# Schematic_skinbot_master_v4.net
KiCad netlist of a schematic drawn in Altium Designer
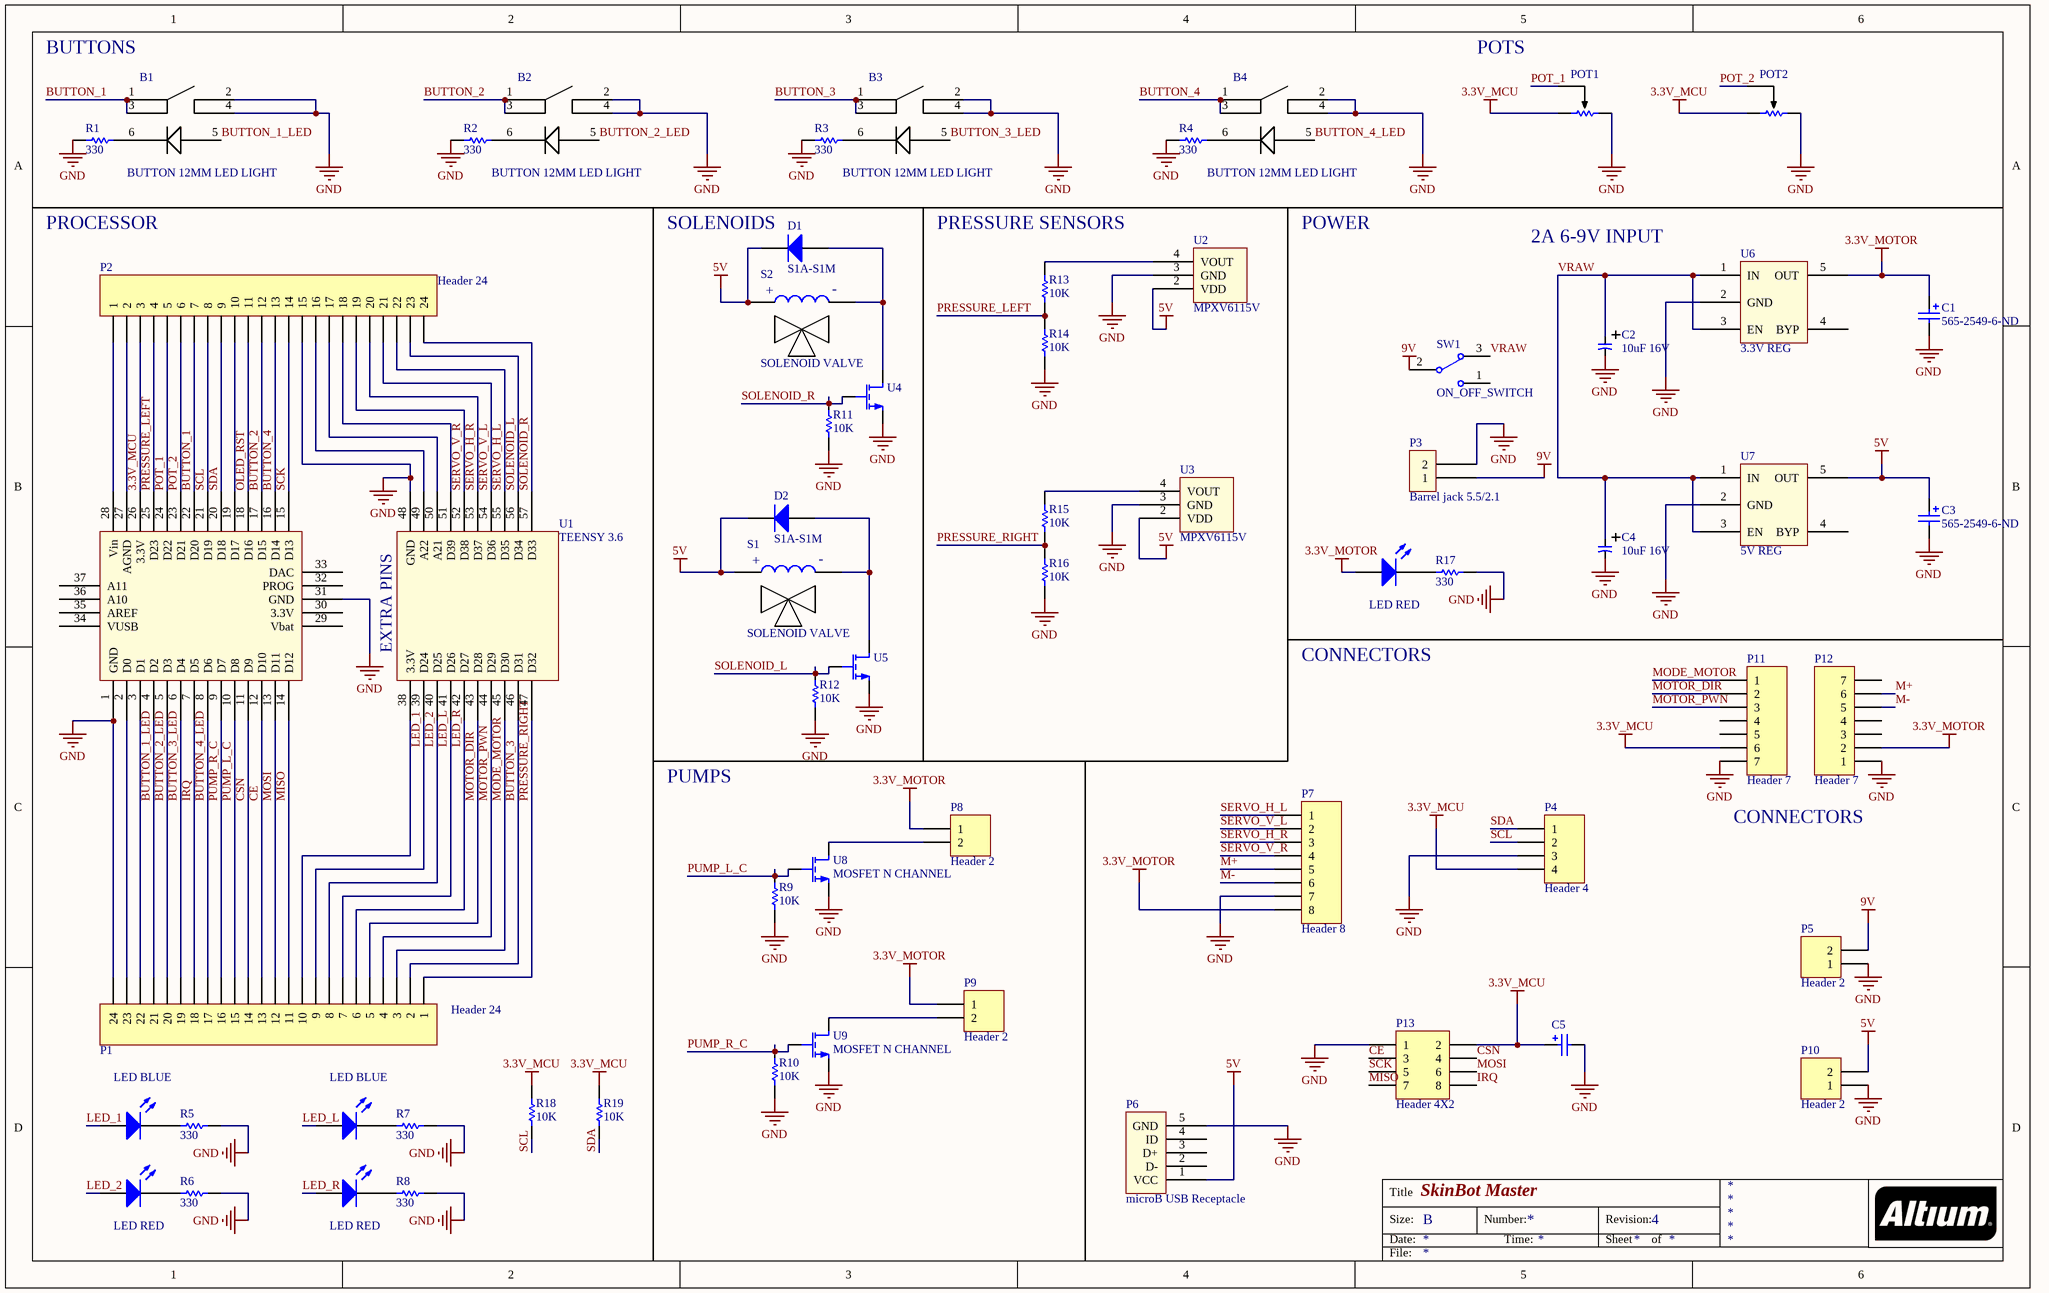
[diagram p0: Schematic_skinbot_master_v4.SchDoc]

(export (version "E")
  (design (tool "Eeschema 10.0.6"))
  (components
    (comp (ref "B1")
      (value "BUTTON 12MM LED LIGHT")
      (footprint "12MM BUTTON LED LIGHT")
      (libsource (lib "Artem_Library") (part "BUTTON 12MM LED LIGHT"))
    )
    (comp (ref "B2")
      (value "BUTTON 12MM LED LIGHT")
      (footprint "12MM BUTTON LED LIGHT")
      (libsource (lib "Artem_Library") (part "BUTTON 12MM LED LIGHT"))
    )
    (comp (ref "B3")
      (value "BUTTON 12MM LED LIGHT")
      (footprint "12MM BUTTON LED LIGHT")
      (libsource (lib "Artem_Library") (part "BUTTON 12MM LED LIGHT"))
    )
    (comp (ref "B4")
      (value "BUTTON 12MM LED LIGHT")
      (footprint "12MM BUTTON LED LIGHT")
      (libsource (lib "Artem_Library") (part "BUTTON 12MM LED LIGHT"))
    )
    (comp (ref "C1")
      (value "Electrolytic Cap 100uF smd")
      (footprint "F80 Electrolytic cap")
      (description "100uF 25 VSMD")
      (fields
        (field (name "DIGIKEY PART NUMBER") "565-2549-1-ND")
        (field (name "MANUFACTURER") "United Chemi-Con")
        (field (name "SUPPLIER PART NUMBER 1") "565-2549-6-ND")
      )
      (libsource (lib "Artem_Library") (part "Electrolytic Cap 100uF smd"))
    )
    (comp (ref "C2")
      (value "10uF 16V")
      (footprint "CAP0805")
      (libsource (lib "Artem_Library") (part "Polarized Cap"))
    )
    (comp (ref "C3")
      (value "Electrolytic Cap 100uF smd")
      (footprint "F80 Electrolytic cap")
      (description "100uF 25 VSMD")
      (fields
        (field (name "DIGIKEY PART NUMBER") "565-2549-1-ND")
        (field (name "MANUFACTURER") "United Chemi-Con")
        (field (name "SUPPLIER PART NUMBER 1") "565-2549-6-ND")
      )
      (libsource (lib "Artem_Library") (part "Electrolytic Cap 100uF smd"))
    )
    (comp (ref "C4")
      (value "10uF 16V")
      (footprint "CAP0805")
      (libsource (lib "Artem_Library") (part "Polarized Cap"))
    )
    (comp (ref "C5")
      (value "Electrolytic Cap 100uF smd")
      (footprint "F80 Electrolytic cap")
      (description "100uF 25 VSMD")
      (fields
        (field (name "DIGIKEY PART NUMBER") "565-2549-1-ND")
        (field (name "MANUFACTURER") "United Chemi-Con")
      )
      (libsource (lib "Artem_Library") (part "Electrolytic Cap 100uF smd"))
    )
    (comp (ref "D1")
      (value "S1A-S1M")
      (footprint "JEDEC DO-214")
      (description "General purpose diode 50V 1A SMA")
      (libsource (lib "Artem_Library") (part "S1A-S1M"))
    )
    (comp (ref "D2")
      (value "S1A-S1M")
      (footprint "JEDEC DO-214")
      (description "General purpose diode 50V 1A SMA")
      (libsource (lib "Artem_Library") (part "S1A-S1M"))
    )
    (comp (ref "LED1")
      (value "LED BLUE")
      (footprint "0603 LED")
      (description "LED SMD 1206/0603")
      (libsource (lib "Artem_Library") (part "LED"))
    )
    (comp (ref "LED2")
      (value "LED RED")
      (footprint "0603 LED")
      (description "LED SMD 1206/0603")
      (libsource (lib "Artem_Library") (part "LED"))
    )
    (comp (ref "LED3")
      (value "LED BLUE")
      (footprint "0603 LED")
      (description "LED SMD 1206/0603")
      (libsource (lib "Artem_Library") (part "LED"))
    )
    (comp (ref "LED4")
      (value "LED RED")
      (footprint "0603 LED")
      (description "LED SMD 1206/0603")
      (libsource (lib "Artem_Library") (part "LED"))
    )
    (comp (ref "LED5")
      (value "LED RED")
      (footprint "0603 LED")
      (description "LED SMD 1206/0603")
      (libsource (lib "Artem_Library") (part "LED"))
    )
    (comp (ref "P1")
      (value "Header 24")
      (footprint "HDR1X24")
      (description "Header, 24-Pin")
      (fields (field (name "PUBLISHER") "Altium Limited"))
      (libsource (lib "") (part "Header 24_1"))
    )
    (comp (ref "P2")
      (value "Header 24")
      (footprint "HDR1X24")
      (description "Header, 24-Pin")
      (fields (field (name "PUBLISHER") "Altium Limited"))
      (libsource (lib "Miscellaneous Connectors") (part "Header 24"))
    )
    (comp (ref "P3")
      (value "Barrel jack 5.5/2.1")
      (footprint "ADC-028-2")
      (fields (field (name "SPARKFUN PART NUMBER") "12748"))
      (libsource (lib "Artem_Library") (part "Barrel jack 5.5/2.1"))
    )
    (comp (ref "P4")
      (value "Header 4")
      (footprint "HDR1X4")
      (description "Header, 4-Pin")
      (fields (field (name "PUBLISHER") "Altium Limited"))
      (libsource (lib "Miscellaneous Connectors") (part "Header 4"))
    )
    (comp (ref "P5")
      (value "Header 2")
      (footprint "HDR1X2")
      (description "Header, 2-Pin")
      (fields (field (name "PUBLISHER") "Altium Limited"))
      (libsource (lib "Miscellaneous Connectors") (part "Header 2"))
    )
    (comp (ref "P6")
      (value "microB USB Receptacle")
      (footprint "MicroB USB Standarad SMT")
      (fields (field (name "MANUFACTURER") "ZX62-B-5PA(11)"))
      (libsource (lib "Artem_Library") (part "microB USB Receptacle"))
    )
    (comp (ref "P7")
      (value "Header 8")
      (footprint "HDR1X8")
      (description "Header, 8-Pin")
      (fields (field (name "PUBLISHER") "Altium Limited"))
      (libsource (lib "Miscellaneous Connectors") (part "Header 8"))
    )
    (comp (ref "P8")
      (value "Header 2")
      (footprint "HDR1X2")
      (description "Header, 2-Pin")
      (fields (field (name "PUBLISHER") "Altium Limited"))
      (libsource (lib "") (part "Header 2_1"))
    )
    (comp (ref "P9")
      (value "Header 2")
      (footprint "HDR1X2")
      (description "Header, 2-Pin")
      (fields (field (name "PUBLISHER") "Altium Limited"))
      (libsource (lib "") (part "Header 2_1"))
    )
    (comp (ref "P10")
      (value "Header 2")
      (footprint "HDR1X2")
      (description "Header, 2-Pin")
      (fields (field (name "PUBLISHER") "Altium Limited"))
      (libsource (lib "Miscellaneous Connectors") (part "Header 2"))
    )
    (comp (ref "P11")
      (value "Header 7")
      (footprint "HDR1X7")
      (description "Header, 7-Pin")
      (fields (field (name "PUBLISHER") "Altium Limited"))
      (libsource (lib "") (part "Header 7_1"))
    )
    (comp (ref "P12")
      (value "Header 7")
      (footprint "HDR1X7")
      (description "Header, 7-Pin")
      (fields (field (name "PUBLISHER") "Altium Limited"))
      (libsource (lib "Miscellaneous Connectors") (part "Header 7"))
    )
    (comp (ref "P13")
      (value "Header 4X2")
      (footprint "HDR2X4")
      (description "Header, 4-Pin, Dual row")
      (fields (field (name "PUBLISHER") "Altium Limited"))
      (libsource (lib "Miscellaneous Connectors") (part "Header 4X2"))
    )
    (comp (ref "POT1")
      (value "Potentiometer large")
      (footprint "PRS11S")
      (description "SMD Large pot for audio")
      (libsource (lib "Artem_Library") (part "Potentiometer large"))
    )
    (comp (ref "POT2")
      (value "Potentiometer large")
      (footprint "PRS11S")
      (description "SMD Large pot for audio")
      (libsource (lib "Artem_Library") (part "Potentiometer large"))
    )
    (comp (ref "R1") (value "330") (footprint "0603W") (libsource (lib "Artem_Library") (part "Resistor")))
    (comp (ref "R2") (value "330") (footprint "0603W") (libsource (lib "Artem_Library") (part "Resistor")))
    (comp (ref "R3") (value "330") (footprint "0603W") (libsource (lib "Artem_Library") (part "Resistor")))
    (comp (ref "R4") (value "330") (footprint "0603W") (libsource (lib "Artem_Library") (part "Resistor")))
    (comp (ref "R5") (value "330") (footprint "0603W") (libsource (lib "Artem_Library") (part "Resistor")))
    (comp (ref "R6") (value "330") (footprint "0603W") (libsource (lib "Artem_Library") (part "Resistor")))
    (comp (ref "R7") (value "330") (footprint "0603W") (libsource (lib "Artem_Library") (part "Resistor")))
    (comp (ref "R8") (value "330") (footprint "0603W") (libsource (lib "Artem_Library") (part "Resistor")))
    (comp (ref "R9") (value "10K") (footprint "0603W") (libsource (lib "Artem_Library") (part "Resistor")))
    (comp (ref "R10") (value "10K") (footprint "0603W") (libsource (lib "Artem_Library") (part "Resistor")))
    (comp (ref "R11") (value "10K") (footprint "0603W") (libsource (lib "Artem_Library") (part "Resistor")))
    (comp (ref "R12") (value "10K") (footprint "0603W") (libsource (lib "Artem_Library") (part "Resistor")))
    (comp (ref "R13") (value "10K") (footprint "0603W") (libsource (lib "Artem_Library") (part "Resistor")))
    (comp (ref "R14") (value "10K") (footprint "0603W") (libsource (lib "Artem_Library") (part "Resistor")))
    (comp (ref "R15") (value "10K") (footprint "0603W") (libsource (lib "Artem_Library") (part "Resistor")))
    (comp (ref "R16") (value "10K") (footprint "0603W") (libsource (lib "Artem_Library") (part "Resistor")))
    (comp (ref "R17") (value "330") (footprint "0603W") (libsource (lib "Artem_Library") (part "Resistor")))
    (comp (ref "R18") (value "10K") (footprint "0603W") (libsource (lib "Artem_Library") (part "Resistor")))
    (comp (ref "R19") (value "10K") (footprint "0603W") (libsource (lib "Artem_Library") (part "Resistor")))
    (comp (ref "S1")
      (value "SOLENOID VALVE")
      (footprint "S070C-5CG-32")
      (libsource (lib "Artem_Library") (part "SOLENOID VALVE"))
    )
    (comp (ref "S2")
      (value "SOLENOID VALVE")
      (footprint "S070C-5CG-32")
      (libsource (lib "Artem_Library") (part "SOLENOID VALVE"))
    )
    (comp (ref "SW1")
      (value "ON_OFF_SWITCH")
      (footprint "SS321 Switch")
      (description "SPDT SMD Side Switch")
      (libsource (lib "Artem_Library") (part "ON_OFF_SWITCH"))
    )
    (comp (ref "U1")
      (value "TEENSY 3.6")
      (footprint "TEENSY 3.6")
      (libsource (lib "Artem_Library") (part "TEENSY 3.6"))
    )
    (comp (ref "U2")
      (value "MPXV6115V")
      (footprint "MPXV6115V")
      (description "Vacuum pressure sensor -115kPa")
      (libsource (lib "Artem_Library") (part "MPXV6115V"))
    )
    (comp (ref "U3")
      (value "MPXV6115V")
      (footprint "MPXV6115V")
      (description "Vacuum pressure sensor -115kPa")
      (libsource (lib "Artem_Library") (part "MPXV6115V"))
    )
    (comp (ref "U4")
      (value "MOSFET N CHANNEL")
      (footprint "SOT323")
      (fields (field (name "DIGIKEY PART NUMBER") "1727-4793-1-ND"))
      (libsource (lib "Artem_Library") (part "MOSFET N CHANNEL"))
    )
    (comp (ref "U5")
      (value "MOSFET N CHANNEL")
      (footprint "SOT323")
      (fields (field (name "DIGIKEY PART NUMBER") "1727-4793-1-ND"))
      (libsource (lib "Artem_Library") (part "MOSFET N CHANNEL"))
    )
    (comp (ref "U6")
      (value "3.3V REG")
      (footprint "SOT-23-5")
      (description "5V LDO SMD")
      (libsource (lib "Artem_Library") (part "MIC5205_VOLTAGE_REG"))
    )
    (comp (ref "U7")
      (value "5V REG")
      (footprint "SOT-23-5")
      (description "5V LDO SMD")
      (libsource (lib "Artem_Library") (part "MIC5205_VOLTAGE_REG"))
    )
    (comp (ref "U8")
      (value "MOSFET N CHANNEL")
      (footprint "SOT323")
      (fields (field (name "DIGIKEY PART NUMBER") "1727-4793-1-ND"))
      (libsource (lib "Artem_Library") (part "MOSFET N CHANNEL"))
    )
    (comp (ref "U9")
      (value "MOSFET N CHANNEL")
      (footprint "SOT323")
      (fields (field (name "DIGIKEY PART NUMBER") "1727-4793-1-ND"))
      (libsource (lib "Artem_Library") (part "MOSFET N CHANNEL"))
    )
  )
  (nets
    (net (code "1") (name "/BUTTON_1") (class "Default")
      (node (ref "B1") (pin "1") (pinfunction "1_1") (pintype "passive"))
      (node (ref "B1") (pin "3") (pinfunction "3_3") (pintype "passive"))
      (node (ref "P2") (pin "7") (pinfunction "7_7") (pintype "passive"))
      (node (ref "U1") (pin "22") (pinfunction "D20_22") (pintype "passive"))
    )
    (net (code "2") (name "/BUTTON_1_LED") (class "Default")
      (node (ref "B1") (pin "5") (pinfunction "5_5") (pintype "passive"))
      (node (ref "P1") (pin "21") (pinfunction "21_21") (pintype "passive"))
      (node (ref "U1") (pin "4") (pinfunction "D2_4") (pintype "passive"))
    )
    (net (code "3") (name "/BUTTON_2") (class "Default")
      (node (ref "B2") (pin "1") (pinfunction "1_1") (pintype "passive"))
      (node (ref "B2") (pin "3") (pinfunction "3_3") (pintype "passive"))
      (node (ref "P2") (pin "12") (pinfunction "12_12") (pintype "passive"))
      (node (ref "U1") (pin "17") (pinfunction "D15_17") (pintype "passive"))
    )
    (net (code "4") (name "/BUTTON_2_LED") (class "Default")
      (node (ref "B2") (pin "5") (pinfunction "5_5") (pintype "passive"))
      (node (ref "P1") (pin "20") (pinfunction "20_20") (pintype "passive"))
      (node (ref "U1") (pin "5") (pinfunction "D3_5") (pintype "passive"))
    )
    (net (code "5") (name "/BUTTON_3") (class "Default")
      (node (ref "B3") (pin "1") (pinfunction "1_1") (pintype "passive"))
      (node (ref "B3") (pin "3") (pinfunction "3_3") (pintype "passive"))
      (node (ref "P1") (pin "2") (pinfunction "2_2") (pintype "passive"))
      (node (ref "U1") (pin "46") (pinfunction "D31_46") (pintype "passive"))
    )
    (net (code "6") (name "/BUTTON_3_LED") (class "Default")
      (node (ref "B3") (pin "5") (pinfunction "5_5") (pintype "passive"))
      (node (ref "P1") (pin "19") (pinfunction "19_19") (pintype "passive"))
      (node (ref "U1") (pin "6") (pinfunction "D4_6") (pintype "passive"))
    )
    (net (code "7") (name "/BUTTON_4") (class "Default")
      (node (ref "B4") (pin "1") (pinfunction "1_1") (pintype "passive"))
      (node (ref "B4") (pin "3") (pinfunction "3_3") (pintype "passive"))
      (node (ref "P2") (pin "13") (pinfunction "13_13") (pintype "passive"))
      (node (ref "U1") (pin "16") (pinfunction "D14_16") (pintype "passive"))
    )
    (net (code "8") (name "/BUTTON_4_LED") (class "Default")
      (node (ref "B4") (pin "5") (pinfunction "5_5") (pintype "passive"))
      (node (ref "P1") (pin "17") (pinfunction "17_17") (pintype "passive"))
      (node (ref "U1") (pin "8") (pinfunction "D6_8") (pintype "passive"))
    )
    (net (code "9") (name "/CE") (class "Default")
      (node (ref "P1") (pin "13") (pinfunction "13_13") (pintype "passive"))
      (node (ref "P13") (pin "3") (pinfunction "3_3") (pintype "passive"))
      (node (ref "U1") (pin "12") (pinfunction "D10_12") (pintype "passive"))
    )
    (net (code "10") (name "/CSN") (class "Default")
      (node (ref "P1") (pin "14") (pinfunction "14_14") (pintype "passive"))
      (node (ref "P13") (pin "4") (pinfunction "4_4") (pintype "passive"))
      (node (ref "U1") (pin "11") (pinfunction "D9_11") (pintype "passive"))
    )
    (net (code "11") (name "/IRQ") (class "Default")
      (node (ref "P1") (pin "18") (pinfunction "18_18") (pintype "passive"))
      (node (ref "P13") (pin "8") (pinfunction "8_8") (pintype "passive"))
      (node (ref "U1") (pin "7") (pinfunction "D5_7") (pintype "passive"))
    )
    (net (code "12") (name "/LED_1") (class "Default")
      (node (ref "LED1") (pin "1") (pinfunction "A_1") (pintype "passive"))
      (node (ref "P1") (pin "9") (pinfunction "9_9") (pintype "passive"))
      (node (ref "U1") (pin "39") (pinfunction "D24_39") (pintype "passive"))
    )
    (net (code "13") (name "/LED_2") (class "Default")
      (node (ref "LED2") (pin "1") (pinfunction "A_1") (pintype "passive"))
      (node (ref "P1") (pin "8") (pinfunction "8_8") (pintype "passive"))
      (node (ref "U1") (pin "40") (pinfunction "D25_40") (pintype "passive"))
    )
    (net (code "14") (name "/LED_L") (class "Default")
      (node (ref "LED3") (pin "1") (pinfunction "A_1") (pintype "passive"))
      (node (ref "P1") (pin "7") (pinfunction "7_7") (pintype "passive"))
      (node (ref "U1") (pin "41") (pinfunction "D26_41") (pintype "passive"))
    )
    (net (code "15") (name "/LED_R") (class "Default")
      (node (ref "LED4") (pin "1") (pinfunction "A_1") (pintype "passive"))
      (node (ref "P1") (pin "6") (pinfunction "6_6") (pintype "passive"))
      (node (ref "U1") (pin "42") (pinfunction "D27_42") (pintype "passive"))
    )
    (net (code "16") (name "/M+") (class "Default")
      (node (ref "P12") (pin "6") (pinfunction "6_6") (pintype "passive"))
      (node (ref "P7") (pin "5") (pinfunction "5_5") (pintype "passive"))
    )
    (net (code "17") (name "/M-") (class "Default")
      (node (ref "P12") (pin "5") (pinfunction "5_5") (pintype "passive"))
      (node (ref "P7") (pin "6") (pinfunction "6_6") (pintype "passive"))
    )
    (net (code "18") (name "/MISO") (class "Default")
      (node (ref "P1") (pin "11") (pinfunction "11_11") (pintype "passive"))
      (node (ref "P13") (pin "7") (pinfunction "7_7") (pintype "passive"))
      (node (ref "U1") (pin "14") (pinfunction "D12_14") (pintype "passive"))
    )
    (net (code "19") (name "/MODE_MOTOR") (class "Default")
      (node (ref "P1") (pin "3") (pinfunction "3_3") (pintype "passive"))
      (node (ref "P11") (pin "1") (pinfunction "1_1") (pintype "passive"))
      (node (ref "U1") (pin "45") (pinfunction "D30_45") (pintype "passive"))
    )
    (net (code "20") (name "/MOSI") (class "Default")
      (node (ref "P1") (pin "12") (pinfunction "12_12") (pintype "passive"))
      (node (ref "P13") (pin "6") (pinfunction "6_6") (pintype "passive"))
      (node (ref "U1") (pin "13") (pinfunction "D11_13") (pintype "passive"))
    )
    (net (code "21") (name "/MOTOR_DIR") (class "Default")
      (node (ref "P1") (pin "5") (pinfunction "5_5") (pintype "passive"))
      (node (ref "P11") (pin "2") (pinfunction "2_2") (pintype "passive"))
      (node (ref "U1") (pin "43") (pinfunction "D28_43") (pintype "passive"))
    )
    (net (code "22") (name "/MOTOR_PWN") (class "Default")
      (node (ref "P1") (pin "4") (pinfunction "4_4") (pintype "passive"))
      (node (ref "P11") (pin "3") (pinfunction "3_3") (pintype "passive"))
      (node (ref "U1") (pin "44") (pinfunction "D29_44") (pintype "passive"))
    )
    (net (code "23") (name "/OLED_RST") (class "Default")
      (node (ref "P2") (pin "11") (pinfunction "11_11") (pintype "passive"))
      (node (ref "U1") (pin "18") (pinfunction "D16_18") (pintype "passive"))
    )
    (net (code "24") (name "/POT_1") (class "Default")
      (node (ref "P2") (pin "5") (pinfunction "5_5") (pintype "passive"))
      (node (ref "POT1") (pin "2") (pinfunction "2_2") (pintype "passive"))
      (node (ref "U1") (pin "24") (pinfunction "D22_24") (pintype "passive"))
    )
    (net (code "25") (name "/POT_2") (class "Default")
      (node (ref "P2") (pin "6") (pinfunction "6_6") (pintype "passive"))
      (node (ref "POT2") (pin "2") (pinfunction "2_2") (pintype "passive"))
      (node (ref "U1") (pin "23") (pinfunction "D21_23") (pintype "passive"))
    )
    (net (code "26") (name "/PRESSURE_LEFT") (class "Default")
      (node (ref "P2") (pin "4") (pinfunction "4_4") (pintype "passive"))
      (node (ref "R13") (pin "2") (pinfunction "2_2") (pintype "passive"))
      (node (ref "R14") (pin "1") (pinfunction "1_1") (pintype "passive"))
      (node (ref "U1") (pin "25") (pinfunction "D23_25") (pintype "passive"))
    )
    (net (code "27") (name "/PRESSURE_RIGHT") (class "Default")
      (node (ref "P1") (pin "1") (pinfunction "1_1") (pintype "passive"))
      (node (ref "R15") (pin "2") (pinfunction "2_2") (pintype "passive"))
      (node (ref "R16") (pin "1") (pinfunction "1_1") (pintype "passive"))
      (node (ref "U1") (pin "47") (pinfunction "D32_47") (pintype "passive"))
    )
    (net (code "28") (name "/PUMP_L_C") (class "Default")
      (node (ref "P1") (pin "15") (pinfunction "15_15") (pintype "passive"))
      (node (ref "R9") (pin "1") (pinfunction "1_1") (pintype "passive"))
      (node (ref "U1") (pin "10") (pinfunction "D8_10") (pintype "passive"))
      (node (ref "U8") (pin "1") (pinfunction "G_1") (pintype "passive"))
    )
    (net (code "29") (name "/PUMP_R_C") (class "Default")
      (node (ref "P1") (pin "16") (pinfunction "16_16") (pintype "passive"))
      (node (ref "R10") (pin "1") (pinfunction "1_1") (pintype "passive"))
      (node (ref "U1") (pin "9") (pinfunction "D7_9") (pintype "passive"))
      (node (ref "U9") (pin "1") (pinfunction "G_1") (pintype "passive"))
    )
    (net (code "30") (name "/SCK") (class "Default")
      (node (ref "P13") (pin "5") (pinfunction "5_5") (pintype "passive"))
      (node (ref "P2") (pin "14") (pinfunction "14_14") (pintype "passive"))
      (node (ref "U1") (pin "15") (pinfunction "D13_15") (pintype "passive"))
    )
    (net (code "31") (name "/SCL") (class "Default")
      (node (ref "P2") (pin "8") (pinfunction "8_8") (pintype "passive"))
      (node (ref "P4") (pin "2") (pinfunction "2_2") (pintype "passive"))
      (node (ref "R18") (pin "2") (pinfunction "2_2") (pintype "passive"))
      (node (ref "U1") (pin "21") (pinfunction "D19_21") (pintype "passive"))
    )
    (net (code "32") (name "/SDA") (class "Default")
      (node (ref "P2") (pin "9") (pinfunction "9_9") (pintype "passive"))
      (node (ref "P4") (pin "1") (pinfunction "1_1") (pintype "passive"))
      (node (ref "R19") (pin "2") (pinfunction "2_2") (pintype "passive"))
      (node (ref "U1") (pin "20") (pinfunction "D18_20") (pintype "passive"))
    )
    (net (code "33") (name "/SERVO_H_L") (class "Default")
      (node (ref "P2") (pin "22") (pinfunction "22_22") (pintype "passive"))
      (node (ref "P7") (pin "1") (pinfunction "1_1") (pintype "passive"))
      (node (ref "U1") (pin "55") (pinfunction "D35_55") (pintype "passive"))
    )
    (net (code "34") (name "/SERVO_H_R") (class "Default")
      (node (ref "P2") (pin "20") (pinfunction "20_20") (pintype "passive"))
      (node (ref "P7") (pin "3") (pinfunction "3_3") (pintype "passive"))
      (node (ref "U1") (pin "53") (pinfunction "D37_53") (pintype "passive"))
    )
    (net (code "35") (name "/SERVO_V_L") (class "Default")
      (node (ref "P2") (pin "21") (pinfunction "21_21") (pintype "passive"))
      (node (ref "P7") (pin "2") (pinfunction "2_2") (pintype "passive"))
      (node (ref "U1") (pin "54") (pinfunction "D36_54") (pintype "passive"))
    )
    (net (code "36") (name "/SERVO_V_R") (class "Default")
      (node (ref "P2") (pin "19") (pinfunction "19_19") (pintype "passive"))
      (node (ref "P7") (pin "4") (pinfunction "4_4") (pintype "passive"))
      (node (ref "U1") (pin "52") (pinfunction "D38_52") (pintype "passive"))
    )
    (net (code "37") (name "/SOLENOID_L") (class "Default")
      (node (ref "P2") (pin "23") (pinfunction "23_23") (pintype "passive"))
      (node (ref "R12") (pin "1") (pinfunction "1_1") (pintype "passive"))
      (node (ref "U1") (pin "56") (pinfunction "D34_56") (pintype "passive"))
      (node (ref "U5") (pin "1") (pinfunction "G_1") (pintype "passive"))
    )
    (net (code "38") (name "/SOLENOID_R") (class "Default")
      (node (ref "P2") (pin "24") (pinfunction "24_24") (pintype "passive"))
      (node (ref "R11") (pin "1") (pinfunction "1_1") (pintype "passive"))
      (node (ref "U1") (pin "57") (pinfunction "D33_57") (pintype "passive"))
      (node (ref "U4") (pin "1") (pinfunction "G_1") (pintype "passive"))
    )
    (net (code "39") (name "/VRAW") (class "Default")
      (node (ref "C2") (pin "1") (pinfunction "1_1") (pintype "passive"))
      (node (ref "C4") (pin "1") (pinfunction "1_1") (pintype "passive"))
      (node (ref "SW1") (pin "3") (pinfunction "3_3") (pintype "passive"))
      (node (ref "U6") (pin "1") (pinfunction "IN_1") (pintype "passive"))
      (node (ref "U6") (pin "3") (pinfunction "EN_3") (pintype "passive"))
      (node (ref "U7") (pin "1") (pinfunction "IN_1") (pintype "passive"))
      (node (ref "U7") (pin "3") (pinfunction "EN_3") (pintype "passive"))
    )
    (net (code "40") (name "3.3V_MCU") (class "Default")
      (node (ref "C5") (pin "1") (pinfunction "1_1") (pintype "passive"))
      (node (ref "P11") (pin "6") (pinfunction "6_6") (pintype "passive"))
      (node (ref "P13") (pin "2") (pinfunction "2_2") (pintype "passive"))
      (node (ref "P2") (pin "3") (pinfunction "3_3") (pintype "passive"))
      (node (ref "P4") (pin "4") (pinfunction "4_4") (pintype "passive"))
      (node (ref "POT1") (pin "1") (pinfunction "1_1") (pintype "passive"))
      (node (ref "POT2") (pin "1") (pinfunction "1_1") (pintype "passive"))
      (node (ref "R18") (pin "1") (pinfunction "1_1") (pintype "passive"))
      (node (ref "R19") (pin "1") (pinfunction "1_1") (pintype "passive"))
      (node (ref "U1") (pin "26") (pinfunction "3.3V_26") (pintype "passive"))
    )
    (net (code "41") (name "3.3V_MOTOR") (class "Default")
      (node (ref "C1") (pin "1") (pinfunction "1_1") (pintype "passive"))
      (node (ref "LED5") (pin "1") (pinfunction "A_1") (pintype "passive"))
      (node (ref "P12") (pin "2") (pinfunction "2_2") (pintype "passive"))
      (node (ref "P7") (pin "8") (pinfunction "8_8") (pintype "passive"))
      (node (ref "P8") (pin "1") (pinfunction "1_1") (pintype "passive"))
      (node (ref "P9") (pin "1") (pinfunction "1_1") (pintype "passive"))
      (node (ref "U6") (pin "5") (pinfunction "OUT_5") (pintype "passive"))
    )
    (net (code "42") (name "5V") (class "Default")
      (node (ref "C3") (pin "1") (pinfunction "1_1") (pintype "passive"))
      (node (ref "D1") (pin "1") (pinfunction "C_1") (pintype "passive"))
      (node (ref "D2") (pin "1") (pinfunction "C_1") (pintype "passive"))
      (node (ref "P10") (pin "2") (pinfunction "2_2") (pintype "passive"))
      (node (ref "P6") (pin "1") (pinfunction "VCC_1") (pintype "passive"))
      (node (ref "S1") (pin "1") (pinfunction "+_1") (pintype "passive"))
      (node (ref "S2") (pin "1") (pinfunction "+_1") (pintype "passive"))
      (node (ref "U2") (pin "2") (pinfunction "VDD_2") (pintype "passive"))
      (node (ref "U3") (pin "2") (pinfunction "VDD_2") (pintype "passive"))
      (node (ref "U7") (pin "5") (pinfunction "OUT_5") (pintype "passive"))
    )
    (net (code "43") (name "9V") (class "Default")
      (node (ref "P3") (pin "1") (pinfunction "1_1") (pintype "passive"))
      (node (ref "P5") (pin "2") (pinfunction "2_2") (pintype "passive"))
      (node (ref "SW1") (pin "2") (pinfunction "2_2") (pintype "passive"))
    )
    (net (code "44") (name "GND") (class "Default")
      (node (ref "B1") (pin "2") (pinfunction "2_2") (pintype "passive"))
      (node (ref "B1") (pin "4") (pinfunction "4_4") (pintype "passive"))
      (node (ref "B2") (pin "2") (pinfunction "2_2") (pintype "passive"))
      (node (ref "B2") (pin "4") (pinfunction "4_4") (pintype "passive"))
      (node (ref "B3") (pin "2") (pinfunction "2_2") (pintype "passive"))
      (node (ref "B3") (pin "4") (pinfunction "4_4") (pintype "passive"))
      (node (ref "B4") (pin "2") (pinfunction "2_2") (pintype "passive"))
      (node (ref "B4") (pin "4") (pinfunction "4_4") (pintype "passive"))
      (node (ref "C1") (pin "2") (pinfunction "2_2") (pintype "passive"))
      (node (ref "C2") (pin "2") (pinfunction "2_2") (pintype "passive"))
      (node (ref "C3") (pin "2") (pinfunction "2_2") (pintype "passive"))
      (node (ref "C4") (pin "2") (pinfunction "2_2") (pintype "passive"))
      (node (ref "C5") (pin "2") (pinfunction "2_2") (pintype "passive"))
      (node (ref "P1") (pin "24") (pinfunction "24_24") (pintype "passive"))
      (node (ref "P10") (pin "1") (pinfunction "1_1") (pintype "passive"))
      (node (ref "P11") (pin "7") (pinfunction "7_7") (pintype "passive"))
      (node (ref "P12") (pin "1") (pinfunction "1_1") (pintype "passive"))
      (node (ref "P13") (pin "1") (pinfunction "1_1") (pintype "passive"))
      (node (ref "P2") (pin "15") (pinfunction "15_15") (pintype "passive"))
      (node (ref "P3") (pin "2") (pinfunction "2_2") (pintype "passive"))
      (node (ref "P4") (pin "3") (pinfunction "3_3") (pintype "passive"))
      (node (ref "P5") (pin "1") (pinfunction "1_1") (pintype "passive"))
      (node (ref "P6") (pin "5") (pinfunction "GND_5") (pintype "passive"))
      (node (ref "P7") (pin "7") (pinfunction "7_7") (pintype "passive"))
      (node (ref "POT1") (pin "3") (pinfunction "3_3") (pintype "passive"))
      (node (ref "POT2") (pin "3") (pinfunction "3_3") (pintype "passive"))
      (node (ref "R1") (pin "2") (pinfunction "2_2") (pintype "passive"))
      (node (ref "R10") (pin "2") (pinfunction "2_2") (pintype "passive"))
      (node (ref "R11") (pin "2") (pinfunction "2_2") (pintype "passive"))
      (node (ref "R12") (pin "2") (pinfunction "2_2") (pintype "passive"))
      (node (ref "R14") (pin "2") (pinfunction "2_2") (pintype "passive"))
      (node (ref "R16") (pin "2") (pinfunction "2_2") (pintype "passive"))
      (node (ref "R17") (pin "1") (pinfunction "1_1") (pintype "passive"))
      (node (ref "R2") (pin "2") (pinfunction "2_2") (pintype "passive"))
      (node (ref "R3") (pin "2") (pinfunction "2_2") (pintype "passive"))
      (node (ref "R4") (pin "2") (pinfunction "2_2") (pintype "passive"))
      (node (ref "R5") (pin "1") (pinfunction "1_1") (pintype "passive"))
      (node (ref "R6") (pin "1") (pinfunction "1_1") (pintype "passive"))
      (node (ref "R7") (pin "1") (pinfunction "1_1") (pintype "passive"))
      (node (ref "R8") (pin "1") (pinfunction "1_1") (pintype "passive"))
      (node (ref "R9") (pin "2") (pinfunction "2_2") (pintype "passive"))
      (node (ref "U1") (pin "1") (pinfunction "GND_1") (pintype "passive"))
      (node (ref "U1") (pin "31") (pinfunction "GND_31") (pintype "passive"))
      (node (ref "U1") (pin "48") (pinfunction "GND_48") (pintype "passive"))
      (node (ref "U2") (pin "3") (pinfunction "GND_3") (pintype "passive"))
      (node (ref "U3") (pin "3") (pinfunction "GND_3") (pintype "passive"))
      (node (ref "U4") (pin "2") (pinfunction "S_2") (pintype "passive"))
      (node (ref "U5") (pin "2") (pinfunction "S_2") (pintype "passive"))
      (node (ref "U6") (pin "2") (pinfunction "GND_2") (pintype "passive"))
      (node (ref "U7") (pin "2") (pinfunction "GND_2") (pintype "passive"))
      (node (ref "U8") (pin "2") (pinfunction "S_2") (pintype "passive"))
      (node (ref "U9") (pin "2") (pinfunction "S_2") (pintype "passive"))
    )
    (net (code "45") (name "Net-(B1-Pad6)") (class "Default")
      (node (ref "B1") (pin "6") (pinfunction "6_6") (pintype "passive"))
      (node (ref "R1") (pin "1") (pinfunction "1_1") (pintype "passive"))
    )
    (net (code "46") (name "Net-(B2-Pad6)") (class "Default")
      (node (ref "B2") (pin "6") (pinfunction "6_6") (pintype "passive"))
      (node (ref "R2") (pin "1") (pinfunction "1_1") (pintype "passive"))
    )
    (net (code "47") (name "Net-(B3-Pad6)") (class "Default")
      (node (ref "B3") (pin "6") (pinfunction "6_6") (pintype "passive"))
      (node (ref "R3") (pin "1") (pinfunction "1_1") (pintype "passive"))
    )
    (net (code "48") (name "Net-(B4-Pad6)") (class "Default")
      (node (ref "B4") (pin "6") (pinfunction "6_6") (pintype "passive"))
      (node (ref "R4") (pin "1") (pinfunction "1_1") (pintype "passive"))
    )
    (net (code "49") (name "Net-(D1-A)") (class "Default")
      (node (ref "D1") (pin "2") (pinfunction "A_2") (pintype "passive"))
      (node (ref "S2") (pin "2") (pinfunction "-_2") (pintype "passive"))
      (node (ref "U4") (pin "3") (pinfunction "D_3") (pintype "passive"))
    )
    (net (code "50") (name "Net-(D2-A)") (class "Default")
      (node (ref "D2") (pin "2") (pinfunction "A_2") (pintype "passive"))
      (node (ref "S1") (pin "2") (pinfunction "-_2") (pintype "passive"))
      (node (ref "U5") (pin "3") (pinfunction "D_3") (pintype "passive"))
    )
    (net (code "51") (name "Net-(LED1-K)") (class "Default")
      (node (ref "LED1") (pin "2") (pinfunction "K_2") (pintype "passive"))
      (node (ref "R5") (pin "2") (pinfunction "2_2") (pintype "passive"))
    )
    (net (code "52") (name "Net-(LED2-K)") (class "Default")
      (node (ref "LED2") (pin "2") (pinfunction "K_2") (pintype "passive"))
      (node (ref "R6") (pin "2") (pinfunction "2_2") (pintype "passive"))
    )
    (net (code "53") (name "Net-(LED3-K)") (class "Default")
      (node (ref "LED3") (pin "2") (pinfunction "K_2") (pintype "passive"))
      (node (ref "R7") (pin "2") (pinfunction "2_2") (pintype "passive"))
    )
    (net (code "54") (name "Net-(LED4-K)") (class "Default")
      (node (ref "LED4") (pin "2") (pinfunction "K_2") (pintype "passive"))
      (node (ref "R8") (pin "2") (pinfunction "2_2") (pintype "passive"))
    )
    (net (code "55") (name "Net-(LED5-K)") (class "Default")
      (node (ref "LED5") (pin "2") (pinfunction "K_2") (pintype "passive"))
      (node (ref "R17") (pin "2") (pinfunction "2_2") (pintype "passive"))
    )
    (net (code "56") (name "Net-(P1-Pad10)") (class "Default")
      (node (ref "P1") (pin "10") (pinfunction "10_10") (pintype "passive"))
      (node (ref "U1") (pin "38") (pinfunction "3.3V_38") (pintype "passive"))
    )
    (net (code "57") (name "Net-(U1-A21)") (class "Default")
      (node (ref "P2") (pin "17") (pinfunction "17_17") (pintype "passive"))
      (node (ref "U1") (pin "50") (pinfunction "A21_50") (pintype "passive"))
    )
    (net (code "58") (name "Net-(U1-A22)") (class "Default")
      (node (ref "P2") (pin "16") (pinfunction "16_16") (pintype "passive"))
      (node (ref "U1") (pin "49") (pinfunction "A22_49") (pintype "passive"))
    )
    (net (code "59") (name "Net-(U1-AGND)") (class "Default")
      (node (ref "P2") (pin "2") (pinfunction "2_2") (pintype "passive"))
      (node (ref "U1") (pin "27") (pinfunction "AGND_27") (pintype "passive"))
    )
    (net (code "60") (name "Net-(U1-D0)") (class "Default")
      (node (ref "P1") (pin "23") (pinfunction "23_23") (pintype "passive"))
      (node (ref "U1") (pin "2") (pinfunction "D0_2") (pintype "passive"))
    )
    (net (code "61") (name "Net-(U1-D1)") (class "Default")
      (node (ref "P1") (pin "22") (pinfunction "22_22") (pintype "passive"))
      (node (ref "U1") (pin "3") (pinfunction "D1_3") (pintype "passive"))
    )
    (net (code "62") (name "Net-(U1-D17)") (class "Default")
      (node (ref "P2") (pin "10") (pinfunction "10_10") (pintype "passive"))
      (node (ref "U1") (pin "19") (pinfunction "D17_19") (pintype "passive"))
    )
    (net (code "63") (name "Net-(U1-D39)") (class "Default")
      (node (ref "P2") (pin "18") (pinfunction "18_18") (pintype "passive"))
      (node (ref "U1") (pin "51") (pinfunction "D39_51") (pintype "passive"))
    )
    (net (code "64") (name "Net-(U1-Vin)") (class "Default")
      (node (ref "P2") (pin "1") (pinfunction "1_1") (pintype "passive"))
      (node (ref "U1") (pin "28") (pinfunction "Vin_28") (pintype "passive"))
    )
    (net (code "65") (name "Net-(U2-VOUT)") (class "Default")
      (node (ref "R13") (pin "1") (pinfunction "1_1") (pintype "passive"))
      (node (ref "U2") (pin "4") (pinfunction "VOUT_4") (pintype "passive"))
    )
    (net (code "66") (name "Net-(U3-VOUT)") (class "Default")
      (node (ref "R15") (pin "1") (pinfunction "1_1") (pintype "passive"))
      (node (ref "U3") (pin "4") (pinfunction "VOUT_4") (pintype "passive"))
    )
    (net (code "67") (name "Net-(U8-D)") (class "Default")
      (node (ref "P8") (pin "2") (pinfunction "2_2") (pintype "passive"))
      (node (ref "U8") (pin "3") (pinfunction "D_3") (pintype "passive"))
    )
    (net (code "68") (name "Net-(U9-D)") (class "Default")
      (node (ref "P9") (pin "2") (pinfunction "2_2") (pintype "passive"))
      (node (ref "U9") (pin "3") (pinfunction "D_3") (pintype "passive"))
    )
    (net (code "69") (name "unconnected-(P6-D+-Pad3)") (class "Default")
      (node (ref "P6") (pin "3") (pinfunction "D+_3") (pintype "passive"))
    )
    (net (code "70") (name "unconnected-(P6-D--Pad2)") (class "Default")
      (node (ref "P6") (pin "2") (pinfunction "D-_2") (pintype "passive"))
    )
    (net (code "71") (name "unconnected-(P6-ID-Pad4)") (class "Default")
      (node (ref "P6") (pin "4") (pinfunction "ID_4") (pintype "passive"))
    )
    (net (code "72") (name "unconnected-(P11-Pad4)") (class "Default")
      (node (ref "P11") (pin "4") (pinfunction "4_4") (pintype "passive"))
    )
    (net (code "73") (name "unconnected-(P11-Pad5)") (class "Default")
      (node (ref "P11") (pin "5") (pinfunction "5_5") (pintype "passive"))
    )
    (net (code "74") (name "unconnected-(P12-Pad3)") (class "Default")
      (node (ref "P12") (pin "3") (pinfunction "3_3") (pintype "passive"))
    )
    (net (code "75") (name "unconnected-(P12-Pad4)") (class "Default")
      (node (ref "P12") (pin "4") (pinfunction "4_4") (pintype "passive"))
    )
    (net (code "76") (name "unconnected-(P12-Pad7)") (class "Default")
      (node (ref "P12") (pin "7") (pinfunction "7_7") (pintype "passive"))
    )
    (net (code "77") (name "unconnected-(SW1-Pad1)") (class "Default")
      (node (ref "SW1") (pin "1") (pinfunction "1_1") (pintype "passive"))
    )
    (net (code "78") (name "unconnected-(U1-3.3V-Pad30)") (class "Default")
      (node (ref "U1") (pin "30") (pinfunction "3.3V_30") (pintype "passive"))
    )
    (net (code "79") (name "unconnected-(U1-A10-Pad36)") (class "Default")
      (node (ref "U1") (pin "36") (pinfunction "A10_36") (pintype "passive"))
    )
    (net (code "80") (name "unconnected-(U1-A11-Pad37)") (class "Default")
      (node (ref "U1") (pin "37") (pinfunction "A11_37") (pintype "passive"))
    )
    (net (code "81") (name "unconnected-(U1-AREF-Pad35)") (class "Default")
      (node (ref "U1") (pin "35") (pinfunction "AREF_35") (pintype "passive"))
    )
    (net (code "82") (name "unconnected-(U1-DAC-Pad33)") (class "Default")
      (node (ref "U1") (pin "33") (pinfunction "DAC_33") (pintype "passive"))
    )
    (net (code "83") (name "unconnected-(U1-PROG-Pad32)") (class "Default")
      (node (ref "U1") (pin "32") (pinfunction "PROG_32") (pintype "passive"))
    )
    (net (code "84") (name "unconnected-(U1-VUSB-Pad34)") (class "Default")
      (node (ref "U1") (pin "34") (pinfunction "VUSB_34") (pintype "passive"))
    )
    (net (code "85") (name "unconnected-(U1-Vbat-Pad29)") (class "Default")
      (node (ref "U1") (pin "29") (pinfunction "Vbat_29") (pintype "passive"))
    )
    (net (code "86") (name "unconnected-(U6-BYP-Pad4)") (class "Default")
      (node (ref "U6") (pin "4") (pinfunction "BYP_4") (pintype "passive"))
    )
    (net (code "87") (name "unconnected-(U7-BYP-Pad4)") (class "Default")
      (node (ref "U7") (pin "4") (pinfunction "BYP_4") (pintype "passive"))
    )
  )
)
